# USR_IO_IPMI.net
KiCad netlist of a schematic drawn in Altium Designer
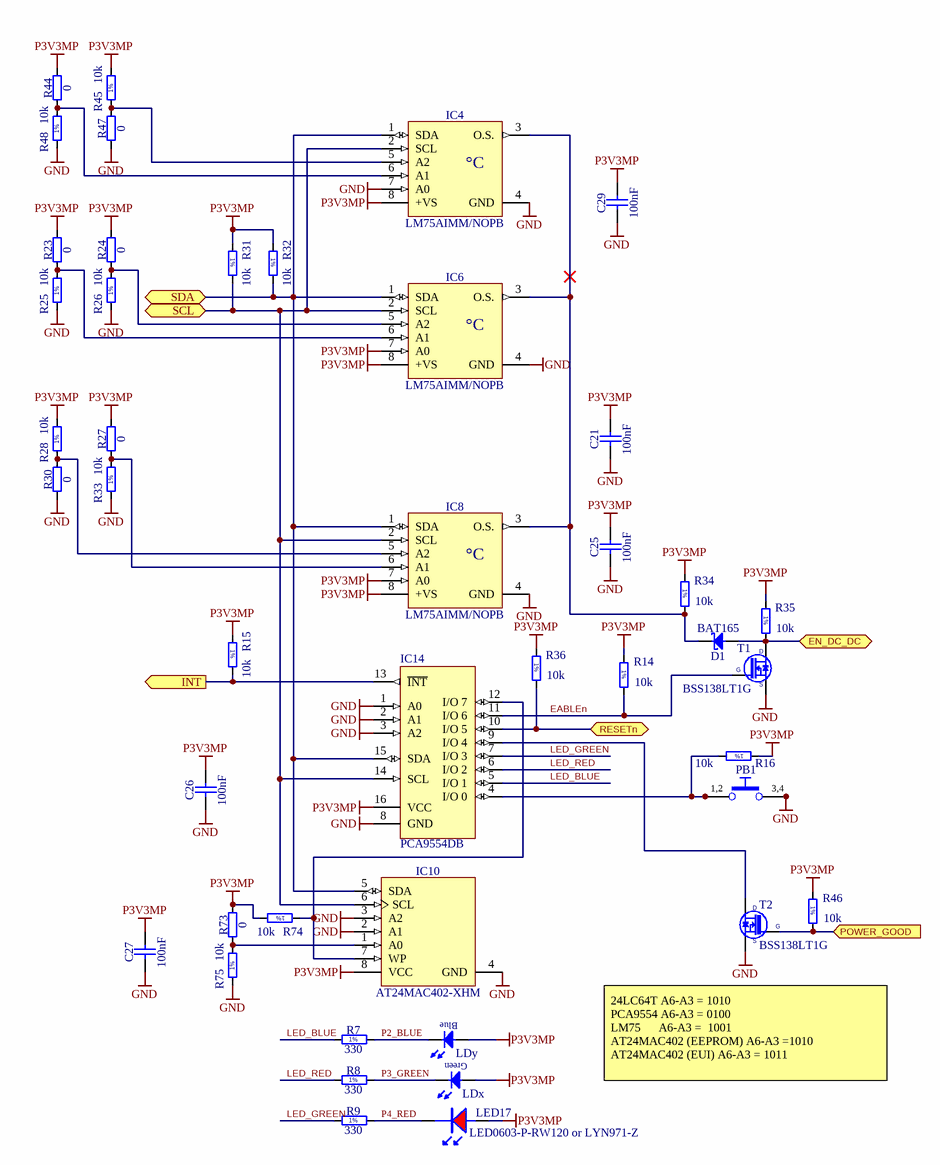
[diagram p0: USR_IO_IPMI.SchDoc]

(export (version "E")
  (design (tool "Eeschema 10.0.6"))
  (components
    (comp (ref "C21")
      (value "100nF")
      (footprint "CAPC1005X55N")
      (description "Non-polarised capacitor")
      (fields
        (field (name "PART NUMBER") "CC0402_100NF_16V_10%_X7R")
        (field (name "VOLTAGE") "16V")
        (field (name "AUTHOR") "CERN DEM JLC")
      )
      (libsource (lib "Capacitors") (part "Capacitor - non polarized"))
    )
    (comp (ref "C25")
      (value "100nF")
      (footprint "CAPC1005X55N")
      (description "Non-polarised capacitor")
      (fields
        (field (name "PART NUMBER") "CC0402_100NF_16V_10%_X7R")
        (field (name "VOLTAGE") "16V")
        (field (name "AUTHOR") "CERN DEM JLC")
      )
      (libsource (lib "Capacitors") (part "Capacitor - non polarized"))
    )
    (comp (ref "C26")
      (value "100nF")
      (footprint "CAPC1005X55N")
      (description "Non-polarised capacitor")
      (fields
        (field (name "PART NUMBER") "CC0402_100NF_16V_10%_X7R")
        (field (name "VOLTAGE") "16V")
        (field (name "AUTHOR") "CERN DEM JLC")
      )
      (libsource (lib "Capacitors") (part "Capacitor - non polarized"))
    )
    (comp (ref "C27")
      (value "100nF")
      (footprint "CAPC1005X55N")
      (description "Non-polarised capacitor")
      (fields
        (field (name "PART NUMBER") "CC0402_100NF_16V_10%_X7R")
        (field (name "VOLTAGE") "16V")
        (field (name "AUTHOR") "CERN DEM JLC")
      )
      (libsource (lib "Capacitors") (part "Capacitor - non polarized"))
    )
    (comp (ref "C29")
      (value "100nF")
      (footprint "CAPC1005X55N")
      (description "Non-polarised capacitor")
      (fields
        (field (name "PART NUMBER") "CC0402_100NF_16V_10%_X7R")
        (field (name "VOLTAGE") "16V")
        (field (name "AUTHOR") "CERN DEM JLC")
      )
      (libsource (lib "Capacitors") (part "Capacitor - non polarized"))
    )
    (comp (ref "D1")
      (value "BAT165")
      (footprint "SOD2512X110N")
      (description "Schottky Diode")
      (fields
        (field (name "MANUFACTURER") "INFINEON")
        (field (name "VOLTAGE") "40V")
        (field (name "AUTHOR") "CERN DEM JLC")
      )
      (libsource (lib "ICs And Semiconductors") (part "Diode Schottky"))
    )
    (comp (ref "IC4")
      (value "LM75AIMM/NOPB")
      (footprint "SOP65P490X109-8N")
      (description "Digital Temperature Sensor and Thermal Watchdog with Two-Wire Interface")
      (fields (field (name "MANUFACTURER") "TEXAS INSTRUMENTS") (field (name "AUTHOR") "CERN DEM JLC"))
      (libsource (lib "ICs And Semiconductors") (part "LM75"))
    )
    (comp (ref "IC6")
      (value "LM75AIMM/NOPB")
      (footprint "SOP65P490X109-8N")
      (description "Digital Temperature Sensor and Thermal Watchdog with Two-Wire Interface")
      (fields (field (name "MANUFACTURER") "TEXAS INSTRUMENTS") (field (name "AUTHOR") "CERN DEM JLC"))
      (libsource (lib "ICs And Semiconductors") (part "LM75"))
    )
    (comp (ref "IC8")
      (value "LM75AIMM/NOPB")
      (footprint "SOP65P490X109-8N")
      (description "Digital Temperature Sensor and Thermal Watchdog with Two-Wire Interface")
      (fields (field (name "MANUFACTURER") "TEXAS INSTRUMENTS") (field (name "AUTHOR") "CERN DEM JLC"))
      (libsource (lib "ICs And Semiconductors") (part "LM75"))
    )
    (comp (ref "IC10")
      (value "AT24MAC402-XHM")
      (footprint "SOP65P640X120-8N")
      (description "1.7V to 5.5V, I2C-Compatible (2-wire) 2-Kbit (256 x 8) Serial EEPROM")
      (fields (field (name "MANUFACTURER") "ATMEL") (field (name "AUTHOR") "CERN DEM MR"))
      (libsource (lib "ICs And Semiconductors") (part "AT24MAC402-XHM"))
    )
    (comp (ref "IC14")
      (value "PCA9554DB")
      (footprint "SOP65P640X120-16N")
      (description "8-bit I2C-bus SMBus I/O port with interrupt")
      (libsource (lib "wr_switch") (part "PCA9554D"))
    )
    (comp (ref "LDx")
      (value "Green")
      (footprint "LED_AVAGO_HSME-C120rev")
      (description "LED Green Avago C120")
      (fields
        (field (name "PART NUMBER") "LED_AVAGO_HSME-C120")
        (field (name "MANUFACTURER") "AVAGO TECHNOLOGIES")
        (field (name "AUTHOR") "CERN DEM JMW")
      )
      (libsource (lib "LIBRARY_SCH") (part "LED_SMD_90deg_mini_G"))
    )
    (comp (ref "LDy")
      (value "Blue")
      (footprint "LED_AVAGO_HSME-C120rev")
      (description "LED Blue Avago C120")
      (fields
        (field (name "PART NUMBER") "LED_AVAGO_HSMR-C120")
        (field (name "MANUFACTURER") "AVAGO TECHNOLOGIES")
        (field (name "AUTHOR") "CERN DEM JMW")
      )
      (libsource (lib "LIBRARY_SCH") (part "LED_SMD_90deg_mini_B"))
    )
    (comp (ref "LED17")
      (value "LED0603-P-RW120 or LYN971-Z")
      (footprint "led_0603R")
      (description "LED 0603 red")
      (libsource (lib "LIBRARY_SCH") (part "LED_0603R"))
    )
    (comp (ref "PB1")
      (value "Push Button")
      (footprint "SW_C&K_HDT0001")
      (description "Push-Button Switch SPDT")
      (fields
        (field (name "PART NUMBER") "SW_C&K_HDT0001")
        (field (name "MANUFACTURER") "C&K")
        (field (name "AUTHOR") "CERN DEM JLC")
      )
      (libsource (lib "Eletro-mechanical") (part "PB SPST 12NO-34NO"))
    )
    (comp (ref "R7")
      (value "330")
      (footprint "RESC1608X55N")
      (description "Resistor - 1%")
      (fields
        (field (name "PART NUMBER") "R0603_330R_1%_0.1W_100PPM")
        (field (name "POWER") "0.1W")
        (field (name "AUTHOR") "CERN DEM JLC")
      )
      (libsource (lib "Resistors") (part "Resistor - 1%"))
    )
    (comp (ref "R8")
      (value "330")
      (footprint "RESC1608X55N")
      (description "Resistor - 1%")
      (fields
        (field (name "PART NUMBER") "R0603_330R_1%_0.1W_100PPM")
        (field (name "POWER") "0.1W")
        (field (name "AUTHOR") "CERN DEM JLC")
      )
      (libsource (lib "Resistors") (part "Resistor - 1%"))
    )
    (comp (ref "R9")
      (value "330")
      (footprint "RESC1608X55N")
      (description "Resistor - 1%")
      (fields
        (field (name "PART NUMBER") "R0603_330R_1%_0.1W_100PPM")
        (field (name "POWER") "0.1W")
        (field (name "AUTHOR") "CERN DEM JLC")
      )
      (libsource (lib "Resistors") (part "Resistor - 1%"))
    )
    (comp (ref "R14")
      (value "10k")
      (footprint "RESC1005X40N")
      (description "Resistor - 1%")
      (fields
        (field (name "PART NUMBER") "R0402_10K_1%_0.0625W_100PPM")
        (field (name "POWER") "0.0625W")
        (field (name "AUTHOR") "CERN DEM JLC")
      )
      (libsource (lib "Resistors") (part "Resistor - 1%"))
    )
    (comp (ref "R15")
      (value "10k")
      (footprint "RESC1005X40N")
      (description "Resistor - 1%")
      (fields
        (field (name "PART NUMBER") "R0402_10K_1%_0.0625W_100PPM")
        (field (name "POWER") "0.0625W")
        (field (name "AUTHOR") "CERN DEM JLC")
      )
      (libsource (lib "Resistors") (part "Resistor - 1%"))
    )
    (comp (ref "R16")
      (value "10k")
      (footprint "RESC1005X40N")
      (description "Resistor - 1%")
      (fields
        (field (name "PART NUMBER") "R0402_10K_1%_0.0625W_100PPM")
        (field (name "POWER") "0.0625W")
        (field (name "AUTHOR") "CERN DEM JLC")
      )
      (libsource (lib "Resistors") (part "Resistor - 1%"))
    )
    (comp (ref "R23")
      (value "0")
      (footprint "RESC1608X55N")
      (description "Resistor")
      (fields
        (field (name "PART NUMBER") "R0603_0R_JUMPER")
        (field (name "MANUFACTURER") "GENERIC")
        (field (name "AUTHOR") "CERN DEM JLC")
      )
      (libsource (lib "Resistors") (part "Resistor"))
    )
    (comp (ref "R24")
      (value "0")
      (footprint "RESC1608X55N")
      (description "Resistor")
      (fields
        (field (name "PART NUMBER") "R0603_0R_JUMPER")
        (field (name "MANUFACTURER") "GENERIC")
        (field (name "AUTHOR") "CERN DEM JLC")
      )
      (libsource (lib "Resistors") (part "Resistor"))
    )
    (comp (ref "R25")
      (value "10k")
      (footprint "RESC1005X40N")
      (description "Resistor - 1%")
      (fields
        (field (name "PART NUMBER") "R0402_10K_1%_0.0625W_100PPM")
        (field (name "POWER") "0.0625W")
        (field (name "AUTHOR") "CERN DEM JLC")
      )
      (libsource (lib "Resistors") (part "Resistor - 1%"))
    )
    (comp (ref "R26")
      (value "10k")
      (footprint "RESC1005X40N")
      (description "Resistor - 1%")
      (fields
        (field (name "PART NUMBER") "R0402_10K_1%_0.0625W_100PPM")
        (field (name "POWER") "0.0625W")
        (field (name "AUTHOR") "CERN DEM JLC")
      )
      (libsource (lib "Resistors") (part "Resistor - 1%"))
    )
    (comp (ref "R27")
      (value "0")
      (footprint "RESC1608X55N")
      (description "Resistor")
      (fields
        (field (name "PART NUMBER") "R0603_0R_JUMPER")
        (field (name "MANUFACTURER") "GENERIC")
        (field (name "AUTHOR") "CERN DEM JLC")
      )
      (libsource (lib "Resistors") (part "Resistor"))
    )
    (comp (ref "R28")
      (value "10k")
      (footprint "RESC1005X40N")
      (description "Resistor - 1%")
      (fields
        (field (name "PART NUMBER") "R0402_10K_1%_0.0625W_100PPM")
        (field (name "POWER") "0.0625W")
        (field (name "AUTHOR") "CERN DEM JLC")
      )
      (libsource (lib "Resistors") (part "Resistor - 1%"))
    )
    (comp (ref "R30")
      (value "0")
      (footprint "RESC1608X55N")
      (description "Resistor")
      (fields
        (field (name "PART NUMBER") "R0603_0R_JUMPER")
        (field (name "MANUFACTURER") "GENERIC")
        (field (name "AUTHOR") "CERN DEM JLC")
      )
      (libsource (lib "Resistors") (part "Resistor"))
    )
    (comp (ref "R31")
      (value "10k")
      (footprint "RESC1005X40N")
      (description "Resistor - 1%")
      (fields
        (field (name "PART NUMBER") "R0402_10K_1%_0.0625W_100PPM")
        (field (name "POWER") "0.0625W")
        (field (name "AUTHOR") "CERN DEM JLC")
      )
      (libsource (lib "Resistors") (part "Resistor - 1%"))
    )
    (comp (ref "R32")
      (value "10k")
      (footprint "RESC1005X40N")
      (description "Resistor - 1%")
      (fields
        (field (name "PART NUMBER") "R0402_10K_1%_0.0625W_100PPM")
        (field (name "POWER") "0.0625W")
        (field (name "AUTHOR") "CERN DEM JLC")
      )
      (libsource (lib "Resistors") (part "Resistor - 1%"))
    )
    (comp (ref "R33")
      (value "10k")
      (footprint "RESC1005X40N")
      (description "Resistor - 1%")
      (fields
        (field (name "PART NUMBER") "R0402_10K_1%_0.0625W_100PPM")
        (field (name "POWER") "0.0625W")
        (field (name "AUTHOR") "CERN DEM JLC")
      )
      (libsource (lib "Resistors") (part "Resistor - 1%"))
    )
    (comp (ref "R34")
      (value "10k")
      (footprint "RESC1005X40N")
      (description "Resistor - 1%")
      (fields
        (field (name "PART NUMBER") "R0402_10K_1%_0.0625W_100PPM")
        (field (name "POWER") "0.0625W")
        (field (name "AUTHOR") "CERN DEM JLC")
      )
      (libsource (lib "Resistors") (part "Resistor - 1%"))
    )
    (comp (ref "R35")
      (value "10k")
      (footprint "RESC1005X40N")
      (description "Resistor - 1%")
      (fields
        (field (name "PART NUMBER") "R0402_10K_1%_0.0625W_100PPM")
        (field (name "POWER") "0.0625W")
        (field (name "AUTHOR") "CERN DEM JLC")
      )
      (libsource (lib "Resistors") (part "Resistor - 1%"))
    )
    (comp (ref "R36")
      (value "10k")
      (footprint "RESC1005X40N")
      (description "Resistor - 1%")
      (fields
        (field (name "PART NUMBER") "R0402_10K_1%_0.0625W_100PPM")
        (field (name "POWER") "0.0625W")
        (field (name "AUTHOR") "CERN DEM JLC")
      )
      (libsource (lib "Resistors") (part "Resistor - 1%"))
    )
    (comp (ref "R44")
      (value "0")
      (footprint "RESC1608X55N")
      (description "Resistor")
      (fields
        (field (name "PART NUMBER") "R0603_0R_JUMPER")
        (field (name "MANUFACTURER") "GENERIC")
        (field (name "AUTHOR") "CERN DEM JLC")
      )
      (libsource (lib "Resistors") (part "Resistor"))
    )
    (comp (ref "R45")
      (value "10k")
      (footprint "RESC1005X40N")
      (description "Resistor - 1%")
      (fields
        (field (name "PART NUMBER") "R0402_10K_1%_0.0625W_100PPM")
        (field (name "POWER") "0.0625W")
        (field (name "AUTHOR") "CERN DEM JLC")
      )
      (libsource (lib "Resistors") (part "Resistor - 1%"))
    )
    (comp (ref "R46")
      (value "10k")
      (footprint "RESC1005X40N")
      (description "Resistor - 1%")
      (fields
        (field (name "PART NUMBER") "R0402_10K_1%_0.0625W_100PPM")
        (field (name "POWER") "0.0625W")
        (field (name "AUTHOR") "CERN DEM JLC")
      )
      (libsource (lib "Resistors") (part "Resistor - 1%"))
    )
    (comp (ref "R47")
      (value "0")
      (footprint "RESC1608X55N")
      (description "Resistor")
      (fields
        (field (name "PART NUMBER") "R0603_0R_JUMPER")
        (field (name "MANUFACTURER") "GENERIC")
        (field (name "AUTHOR") "CERN DEM JLC")
      )
      (libsource (lib "Resistors") (part "Resistor"))
    )
    (comp (ref "R48")
      (value "10k")
      (footprint "RESC1005X40N")
      (description "Resistor - 1%")
      (fields
        (field (name "PART NUMBER") "R0402_10K_1%_0.0625W_100PPM")
        (field (name "POWER") "0.0625W")
        (field (name "AUTHOR") "CERN DEM JLC")
      )
      (libsource (lib "Resistors") (part "Resistor - 1%"))
    )
    (comp (ref "R73")
      (value "0")
      (footprint "RESC1608X55N")
      (description "Resistor")
      (fields
        (field (name "PART NUMBER") "R0603_0R_JUMPER")
        (field (name "MANUFACTURER") "GENERIC")
        (field (name "AUTHOR") "CERN DEM JLC")
      )
      (libsource (lib "Resistors") (part "Resistor"))
    )
    (comp (ref "R74")
      (value "10k")
      (footprint "RESC1005X40N")
      (description "Resistor - 1%")
      (fields
        (field (name "PART NUMBER") "R0402_10K_1%_0.0625W_100PPM")
        (field (name "POWER") "0.0625W")
        (field (name "AUTHOR") "CERN DEM JLC")
      )
      (libsource (lib "Resistors") (part "Resistor - 1%"))
    )
    (comp (ref "R75")
      (value "10k")
      (footprint "RESC1005X40N")
      (description "Resistor - 1%")
      (fields
        (field (name "PART NUMBER") "R0402_10K_1%_0.0625W_100PPM")
        (field (name "POWER") "0.0625W")
        (field (name "AUTHOR") "CERN DEM JLC")
      )
      (libsource (lib "Resistors") (part "Resistor - 1%"))
    )
    (comp (ref "T1")
      (value "BSS138LT1G")
      (footprint "SOT95P240X110-3N")
      (description "N-CHANNEL MOSFET WITH DIODE")
      (fields (field (name "MANUFACTURER") "ON SEMICONDUCTOR") (field (name "AUTHOR") "CERN DEM JLC"))
      (libsource (lib "") (part "N-MOSFET-D 1G 2S 3D_1"))
    )
    (comp (ref "T2")
      (value "BSS138LT1G")
      (footprint "SOT95P240X110-3N")
      (description "N-CHANNEL MOSFET WITH DIODE")
      (fields (field (name "MANUFACTURER") "ON SEMICONDUCTOR") (field (name "AUTHOR") "CERN DEM JLC"))
      (libsource (lib "ICs And Semiconductors") (part "N-MOSFET-D 1G 2S 3D"))
    )
  )
  (nets
    (net (code "1") (name "/EABLEn") (class "Default")
      (node (ref "IC14") (pin "11") (pinfunction "I/O_6_11") (pintype "bidirectional"))
      (node (ref "R14") (pin "2") (pinfunction "2_2") (pintype "passive"))
      (node (ref "T1") (pin "1") (pinfunction "G_1") (pintype "passive"))
    )
    (net (code "2") (name "/EN_DC_DC") (class "Default")
      (node (ref "D1") (pin "2") (pinfunction "A_2") (pintype "passive"))
      (node (ref "R35") (pin "2") (pinfunction "2_2") (pintype "passive"))
      (node (ref "T1") (pin "3") (pinfunction "D_3") (pintype "passive"))
    )
    (net (code "3") (name "/INT") (class "Default")
      (node (ref "IC14") (pin "13") (pinfunction "~{INT}_13") (pintype "output"))
      (node (ref "R15") (pin "2") (pinfunction "2_2") (pintype "passive"))
    )
    (net (code "4") (name "/LED_BLUE") (class "Default")
      (node (ref "IC14") (pin "5") (pinfunction "I/O_1_5") (pintype "bidirectional"))
      (node (ref "R7") (pin "1") (pinfunction "1_1") (pintype "passive"))
    )
    (net (code "5") (name "/LED_GREEN") (class "Default")
      (node (ref "IC14") (pin "7") (pinfunction "I/O_3_7") (pintype "bidirectional"))
      (node (ref "R9") (pin "1") (pinfunction "1_1") (pintype "passive"))
    )
    (net (code "6") (name "/LED_RED") (class "Default")
      (node (ref "IC14") (pin "6") (pinfunction "I/O_2_6") (pintype "bidirectional"))
      (node (ref "R8") (pin "1") (pinfunction "1_1") (pintype "passive"))
    )
    (net (code "7") (name "/P2_BLUE") (class "Default")
      (node (ref "LDy") (pin "2") (pinfunction "C_2") (pintype "passive"))
      (node (ref "R7") (pin "2") (pinfunction "2_2") (pintype "passive"))
    )
    (net (code "8") (name "/P3_GREEN") (class "Default")
      (node (ref "LDx") (pin "2") (pinfunction "C_2") (pintype "passive"))
      (node (ref "R8") (pin "2") (pinfunction "2_2") (pintype "passive"))
    )
    (net (code "9") (name "/P4_RED") (class "Default")
      (node (ref "LED17") (pin "K") (pinfunction "K_K") (pintype "passive"))
      (node (ref "R9") (pin "2") (pinfunction "2_2") (pintype "passive"))
    )
    (net (code "10") (name "/POWER_GOOD") (class "Default")
      (node (ref "R46") (pin "2") (pinfunction "2_2") (pintype "passive"))
      (node (ref "T2") (pin "1") (pinfunction "G_1") (pintype "passive"))
    )
    (net (code "11") (name "/RESETn") (class "Default")
      (node (ref "IC14") (pin "10") (pinfunction "I/O_5_10") (pintype "bidirectional"))
      (node (ref "R36") (pin "2") (pinfunction "2_2") (pintype "passive"))
    )
    (net (code "12") (name "/SCL") (class "Default")
      (node (ref "IC10") (pin "6") (pinfunction "SCL_6") (pintype "input"))
      (node (ref "IC14") (pin "14") (pinfunction "SCL_14") (pintype "input"))
      (node (ref "IC4") (pin "2") (pinfunction "SCL_2") (pintype "input"))
      (node (ref "IC6") (pin "2") (pinfunction "SCL_2") (pintype "input"))
      (node (ref "IC8") (pin "2") (pinfunction "SCL_2") (pintype "input"))
      (node (ref "R31") (pin "2") (pinfunction "2_2") (pintype "passive"))
    )
    (net (code "13") (name "/SDA") (class "Default")
      (node (ref "IC10") (pin "5") (pinfunction "SDA_5") (pintype "bidirectional"))
      (node (ref "IC14") (pin "15") (pinfunction "SDA_15") (pintype "bidirectional"))
      (node (ref "IC4") (pin "1") (pinfunction "SDA_1") (pintype "bidirectional"))
      (node (ref "IC6") (pin "1") (pinfunction "SDA_1") (pintype "bidirectional"))
      (node (ref "IC8") (pin "1") (pinfunction "SDA_1") (pintype "bidirectional"))
      (node (ref "R32") (pin "2") (pinfunction "2_2") (pintype "passive"))
    )
    (net (code "14") (name "GND") (class "Default")
      (node (ref "C21") (pin "2") (pinfunction "2_2") (pintype "passive"))
      (node (ref "C25") (pin "2") (pinfunction "2_2") (pintype "passive"))
      (node (ref "C26") (pin "2") (pinfunction "2_2") (pintype "passive"))
      (node (ref "C27") (pin "2") (pinfunction "2_2") (pintype "passive"))
      (node (ref "C29") (pin "2") (pinfunction "2_2") (pintype "passive"))
      (node (ref "IC10") (pin "2") (pinfunction "A1_2") (pintype "input"))
      (node (ref "IC10") (pin "3") (pinfunction "A2_3") (pintype "input"))
      (node (ref "IC10") (pin "4") (pinfunction "GND_4") (pintype "power_in"))
      (node (ref "IC14") (pin "1") (pinfunction "A0_1") (pintype "input"))
      (node (ref "IC14") (pin "2") (pinfunction "A1_2") (pintype "input"))
      (node (ref "IC14") (pin "3") (pinfunction "A2_3") (pintype "input"))
      (node (ref "IC14") (pin "8") (pinfunction "GND_8") (pintype "power_in"))
      (node (ref "IC4") (pin "4") (pinfunction "GND_4") (pintype "power_in"))
      (node (ref "IC4") (pin "7") (pinfunction "A0_7") (pintype "input"))
      (node (ref "IC6") (pin "4") (pinfunction "GND_4") (pintype "power_in"))
      (node (ref "IC8") (pin "4") (pinfunction "GND_4") (pintype "power_in"))
      (node (ref "PB1") (pin "3") (pinfunction "3_3") (pintype "passive"))
      (node (ref "PB1") (pin "4") (pinfunction "4_4") (pintype "passive"))
      (node (ref "R25") (pin "1") (pinfunction "1_1") (pintype "passive"))
      (node (ref "R26") (pin "1") (pinfunction "1_1") (pintype "passive"))
      (node (ref "R30") (pin "1") (pinfunction "1_1") (pintype "passive"))
      (node (ref "R33") (pin "1") (pinfunction "1_1") (pintype "passive"))
      (node (ref "R47") (pin "1") (pinfunction "1_1") (pintype "passive"))
      (node (ref "R48") (pin "1") (pinfunction "1_1") (pintype "passive"))
      (node (ref "R75") (pin "1") (pinfunction "1_1") (pintype "passive"))
      (node (ref "T1") (pin "2") (pinfunction "S_2") (pintype "passive"))
      (node (ref "T2") (pin "2") (pinfunction "S_2") (pintype "passive"))
    )
    (net (code "15") (name "Net-(D1-C)") (class "Default")
      (node (ref "D1") (pin "1") (pinfunction "C_1") (pintype "passive"))
      (node (ref "IC4") (pin "3") (pinfunction "O.S._3") (pintype "output"))
      (node (ref "IC6") (pin "3") (pinfunction "O.S._3") (pintype "output"))
      (node (ref "IC8") (pin "3") (pinfunction "O.S._3") (pintype "output"))
      (node (ref "R34") (pin "2") (pinfunction "2_2") (pintype "passive"))
    )
    (net (code "16") (name "Net-(IC4-A1)") (class "Default")
      (node (ref "IC4") (pin "6") (pinfunction "A1_6") (pintype "input"))
      (node (ref "R44") (pin "1") (pinfunction "1_1") (pintype "passive"))
      (node (ref "R48") (pin "2") (pinfunction "2_2") (pintype "passive"))
    )
    (net (code "17") (name "Net-(IC4-A2)") (class "Default")
      (node (ref "IC4") (pin "5") (pinfunction "A2_5") (pintype "input"))
      (node (ref "R45") (pin "1") (pinfunction "1_1") (pintype "passive"))
      (node (ref "R47") (pin "2") (pinfunction "2_2") (pintype "passive"))
    )
    (net (code "18") (name "Net-(IC6-A1)") (class "Default")
      (node (ref "IC6") (pin "6") (pinfunction "A1_6") (pintype "input"))
      (node (ref "R23") (pin "1") (pinfunction "1_1") (pintype "passive"))
      (node (ref "R25") (pin "2") (pinfunction "2_2") (pintype "passive"))
    )
    (net (code "19") (name "Net-(IC6-A2)") (class "Default")
      (node (ref "IC6") (pin "5") (pinfunction "A2_5") (pintype "input"))
      (node (ref "R24") (pin "1") (pinfunction "1_1") (pintype "passive"))
      (node (ref "R26") (pin "2") (pinfunction "2_2") (pintype "passive"))
    )
    (net (code "20") (name "Net-(IC8-A1)") (class "Default")
      (node (ref "IC8") (pin "6") (pinfunction "A1_6") (pintype "input"))
      (node (ref "R27") (pin "1") (pinfunction "1_1") (pintype "passive"))
      (node (ref "R33") (pin "2") (pinfunction "2_2") (pintype "passive"))
    )
    (net (code "21") (name "Net-(IC8-A2)") (class "Default")
      (node (ref "IC8") (pin "5") (pinfunction "A2_5") (pintype "input"))
      (node (ref "R28") (pin "1") (pinfunction "1_1") (pintype "passive"))
      (node (ref "R30") (pin "2") (pinfunction "2_2") (pintype "passive"))
    )
    (net (code "22") (name "Net-(IC10-A0)") (class "Default")
      (node (ref "IC10") (pin "1") (pinfunction "A0_1") (pintype "input"))
      (node (ref "R73") (pin "1") (pinfunction "1_1") (pintype "passive"))
      (node (ref "R75") (pin "2") (pinfunction "2_2") (pintype "passive"))
    )
    (net (code "23") (name "Net-(IC10-WP)") (class "Default")
      (node (ref "IC10") (pin "7") (pinfunction "WP_7") (pintype "input"))
      (node (ref "IC14") (pin "12") (pinfunction "I/O_7_12") (pintype "bidirectional"))
      (node (ref "R74") (pin "1") (pinfunction "1_1") (pintype "passive"))
    )
    (net (code "24") (name "Net-(IC14-I{slash}O_0)") (class "Default")
      (node (ref "IC14") (pin "4") (pinfunction "I/O_0_4") (pintype "bidirectional"))
      (node (ref "PB1") (pin "1") (pinfunction "1_1") (pintype "passive"))
      (node (ref "PB1") (pin "2") (pinfunction "2_2") (pintype "passive"))
      (node (ref "R16") (pin "2") (pinfunction "2_2") (pintype "passive"))
    )
    (net (code "25") (name "Net-(IC14-I{slash}O_4)") (class "Default")
      (node (ref "IC14") (pin "9") (pinfunction "I/O_4_9") (pintype "bidirectional"))
      (node (ref "T2") (pin "3") (pinfunction "D_3") (pintype "passive"))
    )
    (net (code "26") (name "P3V3MP") (class "Default")
      (node (ref "C21") (pin "1") (pinfunction "1_1") (pintype "passive"))
      (node (ref "C25") (pin "1") (pinfunction "1_1") (pintype "passive"))
      (node (ref "C26") (pin "1") (pinfunction "1_1") (pintype "passive"))
      (node (ref "C27") (pin "1") (pinfunction "1_1") (pintype "passive"))
      (node (ref "C29") (pin "1") (pinfunction "1_1") (pintype "passive"))
      (node (ref "IC10") (pin "8") (pinfunction "VCC_8") (pintype "power_in"))
      (node (ref "IC14") (pin "16") (pinfunction "VCC_16") (pintype "power_in"))
      (node (ref "IC4") (pin "8") (pinfunction "+VS_8") (pintype "power_in"))
      (node (ref "IC6") (pin "7") (pinfunction "A0_7") (pintype "input"))
      (node (ref "IC6") (pin "8") (pinfunction "+VS_8") (pintype "power_in"))
      (node (ref "IC8") (pin "7") (pinfunction "A0_7") (pintype "input"))
      (node (ref "IC8") (pin "8") (pinfunction "+VS_8") (pintype "power_in"))
      (node (ref "LDx") (pin "1") (pinfunction "A_1") (pintype "passive"))
      (node (ref "LDy") (pin "1") (pinfunction "A_1") (pintype "passive"))
      (node (ref "LED17") (pin "A") (pinfunction "A_A") (pintype "passive"))
      (node (ref "R14") (pin "1") (pinfunction "1_1") (pintype "passive"))
      (node (ref "R15") (pin "1") (pinfunction "1_1") (pintype "passive"))
      (node (ref "R16") (pin "1") (pinfunction "1_1") (pintype "passive"))
      (node (ref "R23") (pin "2") (pinfunction "2_2") (pintype "passive"))
      (node (ref "R24") (pin "2") (pinfunction "2_2") (pintype "passive"))
      (node (ref "R27") (pin "2") (pinfunction "2_2") (pintype "passive"))
      (node (ref "R28") (pin "2") (pinfunction "2_2") (pintype "passive"))
      (node (ref "R31") (pin "1") (pinfunction "1_1") (pintype "passive"))
      (node (ref "R32") (pin "1") (pinfunction "1_1") (pintype "passive"))
      (node (ref "R34") (pin "1") (pinfunction "1_1") (pintype "passive"))
      (node (ref "R35") (pin "1") (pinfunction "1_1") (pintype "passive"))
      (node (ref "R36") (pin "1") (pinfunction "1_1") (pintype "passive"))
      (node (ref "R44") (pin "2") (pinfunction "2_2") (pintype "passive"))
      (node (ref "R45") (pin "2") (pinfunction "2_2") (pintype "passive"))
      (node (ref "R46") (pin "1") (pinfunction "1_1") (pintype "passive"))
      (node (ref "R73") (pin "2") (pinfunction "2_2") (pintype "passive"))
      (node (ref "R74") (pin "2") (pinfunction "2_2") (pintype "passive"))
    )
  )
)
